# Adafruit_Trellis_4x4_3mm_HT16K33.net
KiCad netlist of a schematic drawn in EAGLE
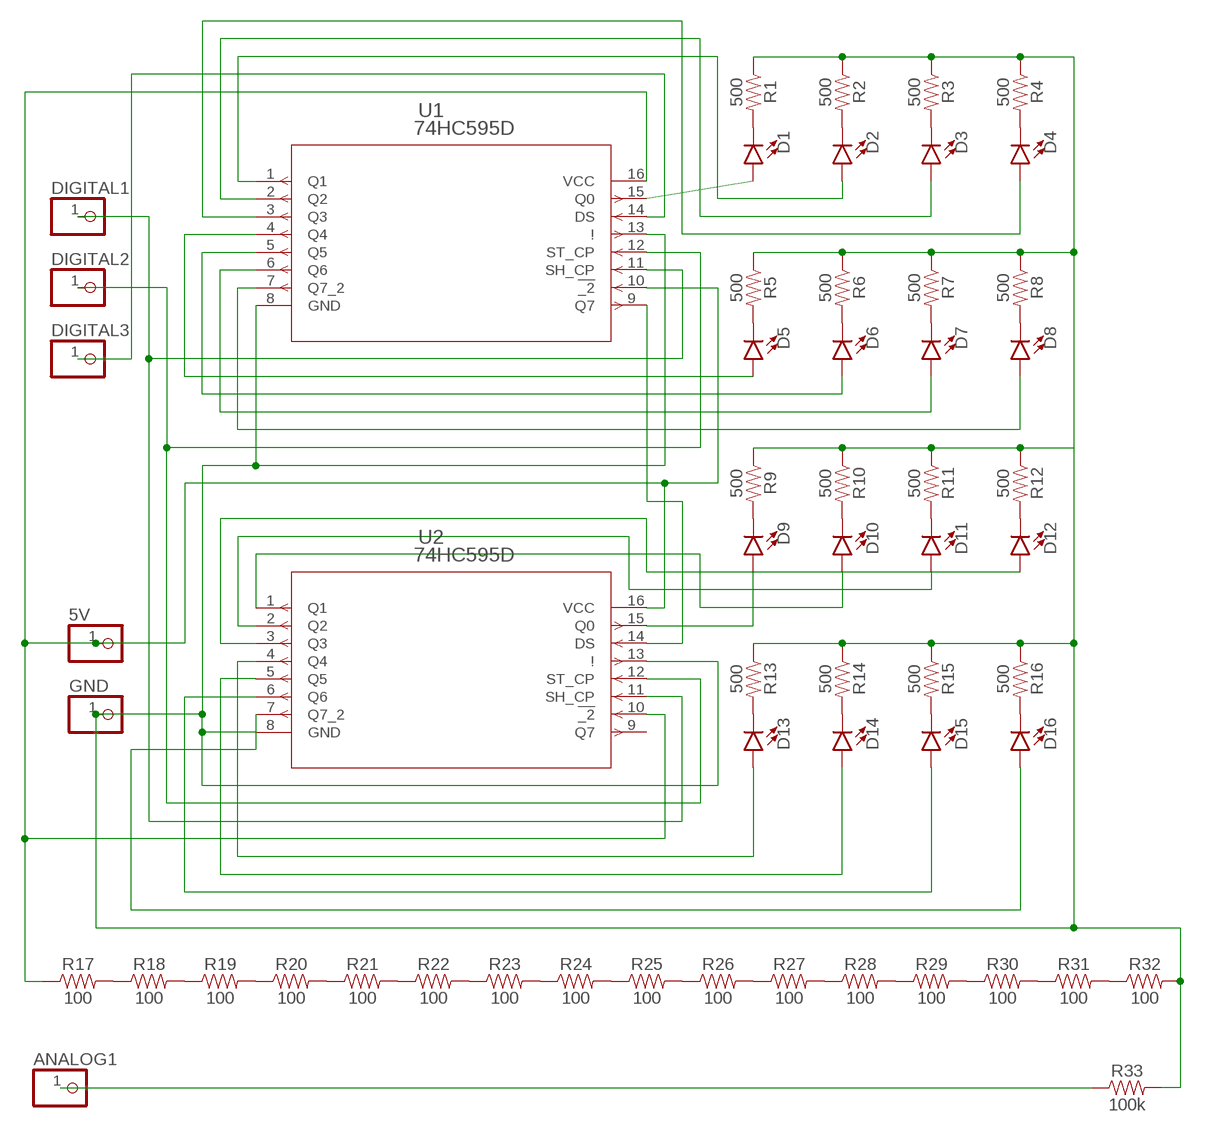
[diagram p0: schematic, sheet 1]

(export (version "E")
  (design (tool "Eeschema 10.0.6"))
  (components
    (comp (ref "5V")
      (value "PINHD-1X1")
      (footprint "eagle-import:1X01")
      (libsource (lib "eagle-import") (part "PINHD-1X1"))
    )
    (comp (ref "ANALOG1")
      (value "PINHD-1X1")
      (footprint "eagle-import:1X01")
      (libsource (lib "eagle-import") (part "PINHD-1X1"))
    )
    (comp (ref "D1")
      (value "LED3MM")
      (footprint "eagle-import:LED_3MM")
      (libsource (lib "eagle-import") (part "LED3MM"))
    )
    (comp (ref "D2")
      (value "LED3MM")
      (footprint "eagle-import:LED_3MM")
      (libsource (lib "eagle-import") (part "LED3MM"))
    )
    (comp (ref "D3")
      (value "LED3MM")
      (footprint "eagle-import:LED_3MM")
      (libsource (lib "eagle-import") (part "LED3MM"))
    )
    (comp (ref "D4")
      (value "LED3MM")
      (footprint "eagle-import:LED_3MM")
      (libsource (lib "eagle-import") (part "LED3MM"))
    )
    (comp (ref "D5")
      (value "LED3MM")
      (footprint "eagle-import:LED_3MM")
      (libsource (lib "eagle-import") (part "LED3MM"))
    )
    (comp (ref "D6")
      (value "LED3MM")
      (footprint "eagle-import:LED_3MM")
      (libsource (lib "eagle-import") (part "LED3MM"))
    )
    (comp (ref "D7")
      (value "LED3MM")
      (footprint "eagle-import:LED_3MM")
      (libsource (lib "eagle-import") (part "LED3MM"))
    )
    (comp (ref "D8")
      (value "LED3MM")
      (footprint "eagle-import:LED_3MM")
      (libsource (lib "eagle-import") (part "LED3MM"))
    )
    (comp (ref "D9")
      (value "LED3MM")
      (footprint "eagle-import:LED_3MM")
      (libsource (lib "eagle-import") (part "LED3MM"))
    )
    (comp (ref "D10")
      (value "LED3MM")
      (footprint "eagle-import:LED_3MM")
      (libsource (lib "eagle-import") (part "LED3MM"))
    )
    (comp (ref "D11")
      (value "LED3MM")
      (footprint "eagle-import:LED_3MM")
      (libsource (lib "eagle-import") (part "LED3MM"))
    )
    (comp (ref "D12")
      (value "LED3MM")
      (footprint "eagle-import:LED_3MM")
      (libsource (lib "eagle-import") (part "LED3MM"))
    )
    (comp (ref "D13")
      (value "LED3MM")
      (footprint "eagle-import:LED_3MM")
      (libsource (lib "eagle-import") (part "LED3MM"))
    )
    (comp (ref "D14")
      (value "LED3MM")
      (footprint "eagle-import:LED_3MM")
      (libsource (lib "eagle-import") (part "LED3MM"))
    )
    (comp (ref "D15")
      (value "LED3MM")
      (footprint "eagle-import:LED_3MM")
      (libsource (lib "eagle-import") (part "LED3MM"))
    )
    (comp (ref "D16")
      (value "LED3MM")
      (footprint "eagle-import:LED_3MM")
      (libsource (lib "eagle-import") (part "LED3MM"))
    )
    (comp (ref "DIGITAL1")
      (value "PINHD-1X1")
      (footprint "eagle-import:1X01")
      (libsource (lib "eagle-import") (part "PINHD-1X1"))
    )
    (comp (ref "DIGITAL2")
      (value "PINHD-1X1")
      (footprint "eagle-import:1X01")
      (libsource (lib "eagle-import") (part "PINHD-1X1"))
    )
    (comp (ref "DIGITAL3")
      (value "PINHD-1X1")
      (footprint "eagle-import:1X01")
      (libsource (lib "eagle-import") (part "PINHD-1X1"))
    )
    (comp (ref "GND")
      (value "PINHD-1X1")
      (footprint "eagle-import:1X01")
      (libsource (lib "eagle-import") (part "PINHD-1X1"))
    )
    (comp (ref "R1")
      (value "500")
      (footprint "eagle-import:0603")
      (libsource (lib "eagle-import") (part "RESISTOR0603"))
    )
    (comp (ref "R2")
      (value "500")
      (footprint "eagle-import:0603")
      (libsource (lib "eagle-import") (part "RESISTOR0603"))
    )
    (comp (ref "R3")
      (value "500")
      (footprint "eagle-import:0603")
      (libsource (lib "eagle-import") (part "RESISTOR0603"))
    )
    (comp (ref "R4")
      (value "500")
      (footprint "eagle-import:0603")
      (libsource (lib "eagle-import") (part "RESISTOR0603"))
    )
    (comp (ref "R5")
      (value "500")
      (footprint "eagle-import:0603")
      (libsource (lib "eagle-import") (part "RESISTOR0603"))
    )
    (comp (ref "R6")
      (value "500")
      (footprint "eagle-import:0603")
      (libsource (lib "eagle-import") (part "RESISTOR0603"))
    )
    (comp (ref "R7")
      (value "500")
      (footprint "eagle-import:0603")
      (libsource (lib "eagle-import") (part "RESISTOR0603"))
    )
    (comp (ref "R8")
      (value "500")
      (footprint "eagle-import:0603")
      (libsource (lib "eagle-import") (part "RESISTOR0603"))
    )
    (comp (ref "R9")
      (value "500")
      (footprint "eagle-import:0603")
      (libsource (lib "eagle-import") (part "RESISTOR0603"))
    )
    (comp (ref "R10")
      (value "500")
      (footprint "eagle-import:0603")
      (libsource (lib "eagle-import") (part "RESISTOR0603"))
    )
    (comp (ref "R11")
      (value "500")
      (footprint "eagle-import:0603")
      (libsource (lib "eagle-import") (part "RESISTOR0603"))
    )
    (comp (ref "R12")
      (value "500")
      (footprint "eagle-import:0603")
      (libsource (lib "eagle-import") (part "RESISTOR0603"))
    )
    (comp (ref "R13")
      (value "500")
      (footprint "eagle-import:0603")
      (libsource (lib "eagle-import") (part "RESISTOR0603"))
    )
    (comp (ref "R14")
      (value "500")
      (footprint "eagle-import:0603")
      (libsource (lib "eagle-import") (part "RESISTOR0603"))
    )
    (comp (ref "R15")
      (value "500")
      (footprint "eagle-import:0603")
      (libsource (lib "eagle-import") (part "RESISTOR0603"))
    )
    (comp (ref "R16")
      (value "500")
      (footprint "eagle-import:0603")
      (libsource (lib "eagle-import") (part "RESISTOR0603"))
    )
    (comp (ref "R17")
      (value "100")
      (footprint "eagle-import:0603")
      (libsource (lib "eagle-import") (part "100OHM-0603-1/10W-1%"))
    )
    (comp (ref "R18")
      (value "100")
      (footprint "eagle-import:0603")
      (libsource (lib "eagle-import") (part "100OHM-0603-1/10W-1%"))
    )
    (comp (ref "R19")
      (value "100")
      (footprint "eagle-import:0603")
      (libsource (lib "eagle-import") (part "100OHM-0603-1/10W-1%"))
    )
    (comp (ref "R20")
      (value "100")
      (footprint "eagle-import:0603")
      (libsource (lib "eagle-import") (part "100OHM-0603-1/10W-1%"))
    )
    (comp (ref "R21")
      (value "100")
      (footprint "eagle-import:0603")
      (libsource (lib "eagle-import") (part "100OHM-0603-1/10W-1%"))
    )
    (comp (ref "R22")
      (value "100")
      (footprint "eagle-import:0603")
      (libsource (lib "eagle-import") (part "100OHM-0603-1/10W-1%"))
    )
    (comp (ref "R23")
      (value "100")
      (footprint "eagle-import:0603")
      (libsource (lib "eagle-import") (part "100OHM-0603-1/10W-1%"))
    )
    (comp (ref "R24")
      (value "100")
      (footprint "eagle-import:0603")
      (libsource (lib "eagle-import") (part "100OHM-0603-1/10W-1%"))
    )
    (comp (ref "R25")
      (value "100")
      (footprint "eagle-import:0603")
      (libsource (lib "eagle-import") (part "100OHM-0603-1/10W-1%"))
    )
    (comp (ref "R26")
      (value "100")
      (footprint "eagle-import:0603")
      (libsource (lib "eagle-import") (part "100OHM-0603-1/10W-1%"))
    )
    (comp (ref "R27")
      (value "100")
      (footprint "eagle-import:0603")
      (libsource (lib "eagle-import") (part "100OHM-0603-1/10W-1%"))
    )
    (comp (ref "R28")
      (value "100")
      (footprint "eagle-import:0603")
      (libsource (lib "eagle-import") (part "100OHM-0603-1/10W-1%"))
    )
    (comp (ref "R29")
      (value "100")
      (footprint "eagle-import:0603")
      (libsource (lib "eagle-import") (part "100OHM-0603-1/10W-1%"))
    )
    (comp (ref "R30")
      (value "100")
      (footprint "eagle-import:0603")
      (libsource (lib "eagle-import") (part "100OHM-0603-1/10W-1%"))
    )
    (comp (ref "R31")
      (value "100")
      (footprint "eagle-import:0603")
      (libsource (lib "eagle-import") (part "100OHM-0603-1/10W-1%"))
    )
    (comp (ref "R32")
      (value "100")
      (footprint "eagle-import:0603")
      (libsource (lib "eagle-import") (part "100OHM-0603-1/10W-1%"))
    )
    (comp (ref "R33")
      (value "100k")
      (footprint "eagle-import:0603")
      (libsource (lib "eagle-import") (part "100KOHM-0603-1/10W-1%"))
    )
    (comp (ref "U1")
      (value "74HC595D")
      (footprint "eagle-import:SOT109-1_NXP")
      (fields (field (name "COPYRIGHT") "Copyright (C) 2022 Ultra Librarian. All rights reserved."))
      (libsource (lib "eagle-import") (part "74HC595D"))
    )
    (comp (ref "U2")
      (value "74HC595D")
      (footprint "eagle-import:SOT109-1_NXP")
      (fields (field (name "COPYRIGHT") "Copyright (C) 2022 Ultra Librarian. All rights reserved."))
      (libsource (lib "eagle-import") (part "74HC595D"))
    )
  )
  (nets
    (net (code "1") (name "Net-(ANALOG1-Pad1)") (class "Default")
      (node (ref "ANALOG1") (pin "1") (pinfunction "1_1") (pintype "passive"))
      (node (ref "R33") (pin "1") (pinfunction "1_1") (pintype "passive"))
    )
    (net (code "2") (name "Net-(D1-C)") (class "Default")
      (node (ref "D1") (pin "K") (pinfunction "C_K") (pintype "passive"))
      (node (ref "R1") (pin "2") (pinfunction "2_2") (pintype "passive"))
    )
    (net (code "3") (name "Net-(D2-C)") (class "Default")
      (node (ref "D2") (pin "K") (pinfunction "C_K") (pintype "passive"))
      (node (ref "R2") (pin "2") (pinfunction "2_2") (pintype "passive"))
    )
    (net (code "4") (name "Net-(D3-C)") (class "Default")
      (node (ref "D3") (pin "K") (pinfunction "C_K") (pintype "passive"))
      (node (ref "R3") (pin "2") (pinfunction "2_2") (pintype "passive"))
    )
    (net (code "5") (name "Net-(D4-C)") (class "Default")
      (node (ref "D4") (pin "K") (pinfunction "C_K") (pintype "passive"))
      (node (ref "R4") (pin "2") (pinfunction "2_2") (pintype "passive"))
    )
    (net (code "6") (name "Net-(D5-C)") (class "Default")
      (node (ref "D5") (pin "K") (pinfunction "C_K") (pintype "passive"))
      (node (ref "R5") (pin "2") (pinfunction "2_2") (pintype "passive"))
    )
    (net (code "7") (name "Net-(D6-C)") (class "Default")
      (node (ref "D6") (pin "K") (pinfunction "C_K") (pintype "passive"))
      (node (ref "R6") (pin "2") (pinfunction "2_2") (pintype "passive"))
    )
    (net (code "8") (name "Net-(D7-C)") (class "Default")
      (node (ref "D7") (pin "K") (pinfunction "C_K") (pintype "passive"))
      (node (ref "R7") (pin "2") (pinfunction "2_2") (pintype "passive"))
    )
    (net (code "9") (name "Net-(D8-C)") (class "Default")
      (node (ref "D8") (pin "K") (pinfunction "C_K") (pintype "passive"))
      (node (ref "R8") (pin "2") (pinfunction "2_2") (pintype "passive"))
    )
    (net (code "10") (name "Net-(D9-C)") (class "Default")
      (node (ref "D9") (pin "K") (pinfunction "C_K") (pintype "passive"))
      (node (ref "R9") (pin "2") (pinfunction "2_2") (pintype "passive"))
    )
    (net (code "11") (name "Net-(D10-C)") (class "Default")
      (node (ref "D10") (pin "K") (pinfunction "C_K") (pintype "passive"))
      (node (ref "R10") (pin "2") (pinfunction "2_2") (pintype "passive"))
    )
    (net (code "12") (name "Net-(D11-C)") (class "Default")
      (node (ref "D11") (pin "K") (pinfunction "C_K") (pintype "passive"))
      (node (ref "R11") (pin "2") (pinfunction "2_2") (pintype "passive"))
    )
    (net (code "13") (name "Net-(D12-C)") (class "Default")
      (node (ref "D12") (pin "K") (pinfunction "C_K") (pintype "passive"))
      (node (ref "R12") (pin "2") (pinfunction "2_2") (pintype "passive"))
    )
    (net (code "14") (name "Net-(D13-C)") (class "Default")
      (node (ref "D13") (pin "K") (pinfunction "C_K") (pintype "passive"))
      (node (ref "R13") (pin "2") (pinfunction "2_2") (pintype "passive"))
    )
    (net (code "15") (name "Net-(D14-C)") (class "Default")
      (node (ref "D14") (pin "K") (pinfunction "C_K") (pintype "passive"))
      (node (ref "R14") (pin "2") (pinfunction "2_2") (pintype "passive"))
    )
    (net (code "16") (name "Net-(D15-C)") (class "Default")
      (node (ref "D15") (pin "K") (pinfunction "C_K") (pintype "passive"))
      (node (ref "R15") (pin "2") (pinfunction "2_2") (pintype "passive"))
    )
    (net (code "17") (name "Net-(D16-C)") (class "Default")
      (node (ref "D16") (pin "K") (pinfunction "C_K") (pintype "passive"))
      (node (ref "R16") (pin "2") (pinfunction "2_2") (pintype "passive"))
    )
    (net (code "18") (name "Net-(R17-Pad2)") (class "Default")
      (node (ref "R17") (pin "2") (pinfunction "2_2") (pintype "passive"))
      (node (ref "R18") (pin "1") (pinfunction "1_1") (pintype "passive"))
    )
    (net (code "19") (name "Net-(R18-Pad2)") (class "Default")
      (node (ref "R18") (pin "2") (pinfunction "2_2") (pintype "passive"))
      (node (ref "R19") (pin "1") (pinfunction "1_1") (pintype "passive"))
    )
    (net (code "20") (name "Net-(R19-Pad2)") (class "Default")
      (node (ref "R19") (pin "2") (pinfunction "2_2") (pintype "passive"))
      (node (ref "R20") (pin "1") (pinfunction "1_1") (pintype "passive"))
    )
    (net (code "21") (name "Net-(R20-Pad2)") (class "Default")
      (node (ref "R20") (pin "2") (pinfunction "2_2") (pintype "passive"))
      (node (ref "R21") (pin "1") (pinfunction "1_1") (pintype "passive"))
    )
    (net (code "22") (name "Net-(R21-Pad2)") (class "Default")
      (node (ref "R21") (pin "2") (pinfunction "2_2") (pintype "passive"))
      (node (ref "R22") (pin "1") (pinfunction "1_1") (pintype "passive"))
    )
    (net (code "23") (name "Net-(R22-Pad2)") (class "Default")
      (node (ref "R22") (pin "2") (pinfunction "2_2") (pintype "passive"))
      (node (ref "R23") (pin "1") (pinfunction "1_1") (pintype "passive"))
    )
    (net (code "24") (name "Net-(R23-Pad2)") (class "Default")
      (node (ref "R23") (pin "2") (pinfunction "2_2") (pintype "passive"))
      (node (ref "R24") (pin "1") (pinfunction "1_1") (pintype "passive"))
    )
    (net (code "25") (name "Net-(R24-Pad2)") (class "Default")
      (node (ref "R24") (pin "2") (pinfunction "2_2") (pintype "passive"))
      (node (ref "R25") (pin "1") (pinfunction "1_1") (pintype "passive"))
    )
    (net (code "26") (name "Net-(R25-Pad2)") (class "Default")
      (node (ref "R25") (pin "2") (pinfunction "2_2") (pintype "passive"))
      (node (ref "R26") (pin "1") (pinfunction "1_1") (pintype "passive"))
    )
    (net (code "27") (name "Net-(R26-Pad2)") (class "Default")
      (node (ref "R26") (pin "2") (pinfunction "2_2") (pintype "passive"))
      (node (ref "R27") (pin "1") (pinfunction "1_1") (pintype "passive"))
    )
    (net (code "28") (name "Net-(R27-Pad2)") (class "Default")
      (node (ref "R27") (pin "2") (pinfunction "2_2") (pintype "passive"))
      (node (ref "R28") (pin "1") (pinfunction "1_1") (pintype "passive"))
    )
    (net (code "29") (name "Net-(R28-Pad2)") (class "Default")
      (node (ref "R28") (pin "2") (pinfunction "2_2") (pintype "passive"))
      (node (ref "R29") (pin "1") (pinfunction "1_1") (pintype "passive"))
    )
    (net (code "30") (name "Net-(R29-Pad2)") (class "Default")
      (node (ref "R29") (pin "2") (pinfunction "2_2") (pintype "passive"))
      (node (ref "R30") (pin "1") (pinfunction "1_1") (pintype "passive"))
    )
    (net (code "31") (name "Net-(R30-Pad2)") (class "Default")
      (node (ref "R30") (pin "2") (pinfunction "2_2") (pintype "passive"))
      (node (ref "R31") (pin "1") (pinfunction "1_1") (pintype "passive"))
    )
    (net (code "32") (name "Net-(R31-Pad2)") (class "Default")
      (node (ref "R31") (pin "2") (pinfunction "2_2") (pintype "passive"))
      (node (ref "R32") (pin "1") (pinfunction "1_1") (pintype "passive"))
    )
    (net (code "33") (name "Net-(U1-DS)") (class "Default")
      (node (ref "DIGITAL3") (pin "1") (pinfunction "1_1") (pintype "passive"))
      (node (ref "U1") (pin "14") (pinfunction "DS_14") (pintype "input"))
    )
    (net (code "34") (name "Net-(U1-GND)") (class "Default")
      (node (ref "GND") (pin "1") (pinfunction "1_1") (pintype "passive"))
      (node (ref "R1") (pin "1") (pinfunction "1_1") (pintype "passive"))
      (node (ref "R10") (pin "1") (pinfunction "1_1") (pintype "passive"))
      (node (ref "R11") (pin "1") (pinfunction "1_1") (pintype "passive"))
      (node (ref "R12") (pin "1") (pinfunction "1_1") (pintype "passive"))
      (node (ref "R13") (pin "1") (pinfunction "1_1") (pintype "passive"))
      (node (ref "R14") (pin "1") (pinfunction "1_1") (pintype "passive"))
      (node (ref "R15") (pin "1") (pinfunction "1_1") (pintype "passive"))
      (node (ref "R16") (pin "1") (pinfunction "1_1") (pintype "passive"))
      (node (ref "R2") (pin "1") (pinfunction "1_1") (pintype "passive"))
      (node (ref "R3") (pin "1") (pinfunction "1_1") (pintype "passive"))
      (node (ref "R32") (pin "2") (pinfunction "2_2") (pintype "passive"))
      (node (ref "R33") (pin "2") (pinfunction "2_2") (pintype "passive"))
      (node (ref "R4") (pin "1") (pinfunction "1_1") (pintype "passive"))
      (node (ref "R5") (pin "1") (pinfunction "1_1") (pintype "passive"))
      (node (ref "R6") (pin "1") (pinfunction "1_1") (pintype "passive"))
      (node (ref "R7") (pin "1") (pinfunction "1_1") (pintype "passive"))
      (node (ref "R8") (pin "1") (pinfunction "1_1") (pintype "passive"))
      (node (ref "R9") (pin "1") (pinfunction "1_1") (pintype "passive"))
      (node (ref "U1") (pin "13") (pinfunction "~_13") (pintype "output"))
      (node (ref "U1") (pin "8") (pinfunction "GND_8") (pintype "power_in"))
      (node (ref "U2") (pin "13") (pinfunction "~_13") (pintype "output"))
      (node (ref "U2") (pin "8") (pinfunction "GND_8") (pintype "power_in"))
    )
    (net (code "35") (name "Net-(U1-Q0)") (class "Default")
      (node (ref "D1") (pin "A") (pinfunction "A_A") (pintype "passive"))
      (node (ref "U1") (pin "15") (pinfunction "Q0_15") (pintype "output"))
    )
    (net (code "36") (name "Net-(U1-Q1)") (class "Default")
      (node (ref "D2") (pin "A") (pinfunction "A_A") (pintype "passive"))
      (node (ref "U1") (pin "1") (pinfunction "Q1_1") (pintype "output"))
    )
    (net (code "37") (name "Net-(U1-Q2)") (class "Default")
      (node (ref "D3") (pin "A") (pinfunction "A_A") (pintype "passive"))
      (node (ref "U1") (pin "2") (pinfunction "Q2_2") (pintype "output"))
    )
    (net (code "38") (name "Net-(U1-Q3)") (class "Default")
      (node (ref "D4") (pin "A") (pinfunction "A_A") (pintype "passive"))
      (node (ref "U1") (pin "3") (pinfunction "Q3_3") (pintype "output"))
    )
    (net (code "39") (name "Net-(U1-Q4)") (class "Default")
      (node (ref "D5") (pin "A") (pinfunction "A_A") (pintype "passive"))
      (node (ref "U1") (pin "4") (pinfunction "Q4_4") (pintype "output"))
    )
    (net (code "40") (name "Net-(U1-Q5)") (class "Default")
      (node (ref "D6") (pin "A") (pinfunction "A_A") (pintype "passive"))
      (node (ref "U1") (pin "5") (pinfunction "Q5_5") (pintype "output"))
    )
    (net (code "41") (name "Net-(U1-Q6)") (class "Default")
      (node (ref "D7") (pin "A") (pinfunction "A_A") (pintype "passive"))
      (node (ref "U1") (pin "6") (pinfunction "Q6_6") (pintype "output"))
    )
    (net (code "42") (name "Net-(U1-Q7)") (class "Default")
      (node (ref "U1") (pin "9") (pinfunction "Q7_9") (pintype "output"))
      (node (ref "U2") (pin "14") (pinfunction "DS_14") (pintype "input"))
    )
    (net (code "43") (name "Net-(U1-Q7_2)") (class "Default")
      (node (ref "D8") (pin "A") (pinfunction "A_A") (pintype "passive"))
      (node (ref "U1") (pin "7") (pinfunction "Q7_2_7") (pintype "output"))
    )
    (net (code "44") (name "Net-(U1-SH_CP)") (class "Default")
      (node (ref "DIGITAL1") (pin "1") (pinfunction "1_1") (pintype "passive"))
      (node (ref "U1") (pin "11") (pinfunction "SH_CP_11") (pintype "input"))
      (node (ref "U2") (pin "11") (pinfunction "SH_CP_11") (pintype "input"))
    )
    (net (code "45") (name "Net-(U1-ST_CP)") (class "Default")
      (node (ref "DIGITAL2") (pin "1") (pinfunction "1_1") (pintype "passive"))
      (node (ref "U1") (pin "12") (pinfunction "ST_CP_12") (pintype "input"))
      (node (ref "U2") (pin "12") (pinfunction "ST_CP_12") (pintype "input"))
    )
    (net (code "46") (name "Net-(U1-VCC)") (class "Default")
      (node (ref "5V") (pin "1") (pinfunction "1_1") (pintype "passive"))
      (node (ref "R17") (pin "1") (pinfunction "1_1") (pintype "passive"))
      (node (ref "U1") (pin "10") (pinfunction "~{_2}_10") (pintype "input"))
      (node (ref "U1") (pin "16") (pinfunction "VCC_16") (pintype "power_in"))
      (node (ref "U2") (pin "10") (pinfunction "~{_2}_10") (pintype "input"))
      (node (ref "U2") (pin "16") (pinfunction "VCC_16") (pintype "power_in"))
    )
    (net (code "47") (name "Net-(U2-Q0)") (class "Default")
      (node (ref "D9") (pin "A") (pinfunction "A_A") (pintype "passive"))
      (node (ref "U2") (pin "15") (pinfunction "Q0_15") (pintype "output"))
    )
    (net (code "48") (name "Net-(U2-Q1)") (class "Default")
      (node (ref "D10") (pin "A") (pinfunction "A_A") (pintype "passive"))
      (node (ref "U2") (pin "1") (pinfunction "Q1_1") (pintype "output"))
    )
    (net (code "49") (name "Net-(U2-Q2)") (class "Default")
      (node (ref "D11") (pin "A") (pinfunction "A_A") (pintype "passive"))
      (node (ref "U2") (pin "2") (pinfunction "Q2_2") (pintype "output"))
    )
    (net (code "50") (name "Net-(U2-Q3)") (class "Default")
      (node (ref "D12") (pin "A") (pinfunction "A_A") (pintype "passive"))
      (node (ref "U2") (pin "3") (pinfunction "Q3_3") (pintype "output"))
    )
    (net (code "51") (name "Net-(U2-Q4)") (class "Default")
      (node (ref "D13") (pin "A") (pinfunction "A_A") (pintype "passive"))
      (node (ref "U2") (pin "4") (pinfunction "Q4_4") (pintype "output"))
    )
    (net (code "52") (name "Net-(U2-Q5)") (class "Default")
      (node (ref "D14") (pin "A") (pinfunction "A_A") (pintype "passive"))
      (node (ref "U2") (pin "5") (pinfunction "Q5_5") (pintype "output"))
    )
    (net (code "53") (name "Net-(U2-Q6)") (class "Default")
      (node (ref "D15") (pin "A") (pinfunction "A_A") (pintype "passive"))
      (node (ref "U2") (pin "6") (pinfunction "Q6_6") (pintype "output"))
    )
    (net (code "54") (name "Net-(U2-Q7_2)") (class "Default")
      (node (ref "D16") (pin "A") (pinfunction "A_A") (pintype "passive"))
      (node (ref "U2") (pin "7") (pinfunction "Q7_2_7") (pintype "output"))
    )
    (net (code "55") (name "unconnected-(U2-Q7-Pad9)") (class "Default")
      (node (ref "U2") (pin "9") (pinfunction "Q7_9") (pintype "output"))
    )
  )
)
